# Millable_AS726x_Breakout.net
KiCad netlist of a schematic drawn in EAGLE
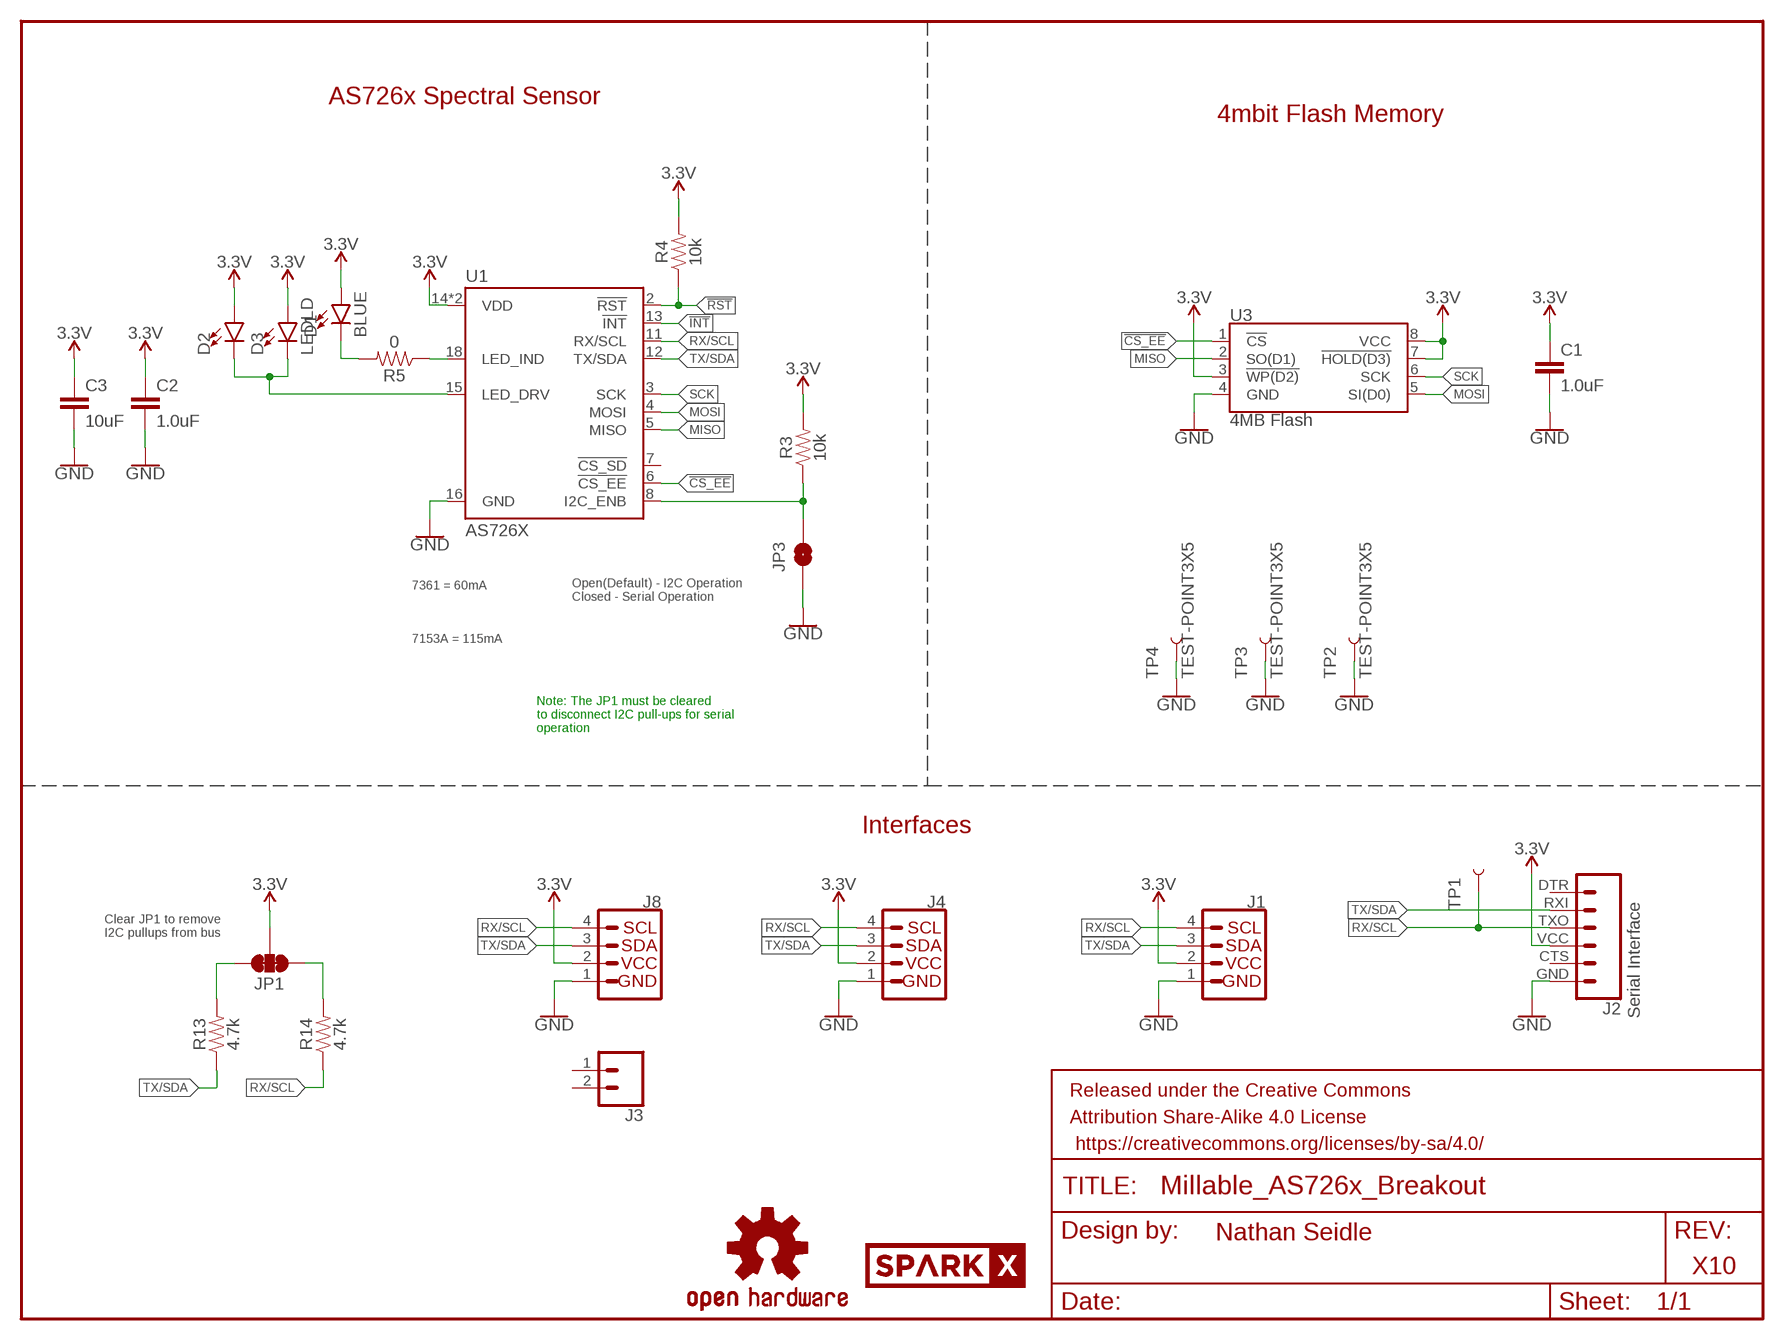
[diagram p0: schematic, sheet 1]

(export (version "E")
  (design (tool "Eeschema 10.0.6"))
  (components
    (comp (ref "C1")
      (value "1.0uF")
      (footprint "eagle-import:0603")
      (libsource (lib "eagle-import") (part "1.0UF-0603-16V-10%"))
    )
    (comp (ref "C2")
      (value "1.0uF")
      (footprint "eagle-import:0603")
      (libsource (lib "eagle-import") (part "1.0UF-0603-16V-10%"))
    )
    (comp (ref "C3")
      (value "10uF")
      (footprint "eagle-import:0603")
      (libsource (lib "eagle-import") (part "10UF-0603-6.3V-20%"))
    )
    (comp (ref "D1")
      (value "BLUE")
      (footprint "eagle-import:LED-0603")
      (libsource (lib "eagle-import") (part "LED-BLUE0603"))
    )
    (comp (ref "D2")
      (value "LED5MM")
      (footprint "eagle-import:LED_5MM")
      (libsource (lib "eagle-import") (part "LED5MM"))
    )
    (comp (ref "D3")
      (value "LEDLD")
      (footprint "eagle-import:SUPER_BRIGHT_SMD_LED_1206")
      (libsource (lib "eagle-import") (part "LEDLD"))
    )
    (comp (ref "FRAME1")
      (value "FRAME-LETTER")
      (footprint "eagle-import:CREATIVE_COMMONS")
      (libsource (lib "eagle-import") (part "FRAME-LETTER"))
    )
    (comp (ref "J1")
      (value "I2C_STANDARDJS-1MM")
      (footprint "eagle-import:1X04_1MM_RA")
      (libsource (lib "eagle-import") (part "I2C_STANDARDJS-1MM"))
    )
    (comp (ref "J2")
      (value "Serial Interface")
      (footprint "eagle-import:FTDI_BASIC")
      (libsource (lib "eagle-import") (part "6_PIN_SERIAL_CABLEPTH"))
    )
    (comp (ref "J3")
      (value "CONN_021X02_NO_SILK")
      (footprint "eagle-import:1X02_NO_SILK")
      (libsource (lib "eagle-import") (part "CONN_021X02_NO_SILK"))
    )
    (comp (ref "J4")
      (value "I2C_STANDARDJS-1MM")
      (footprint "eagle-import:1X04_1MM_RA")
      (libsource (lib "eagle-import") (part "I2C_STANDARDJS-1MM"))
    )
    (comp (ref "J8")
      (value "I2C_STANDARD_NO_SILK")
      (footprint "eagle-import:1X04_NO_SILK")
      (libsource (lib "eagle-import") (part "I2C_STANDARD_NO_SILK"))
    )
    (comp (ref "JP1")
      (value "JUMPER-SMT_3_2-NC_TRACE_SILK")
      (footprint "eagle-import:SMT-JUMPER_3_2-NC_TRACE_SILK")
      (libsource (lib "eagle-import") (part "JUMPER-SMT_3_2-NC_TRACE_SILK"))
    )
    (comp (ref "JP3")
      (value "JUMPER-SMT_2_NO-MILLABLE_NO-SILK")
      (footprint "eagle-import:SMT-JUMPER_2_NO_NO-SILK")
      (libsource (lib "eagle-import") (part "JUMPER-SMT_2_NO-MILLABLE_NO-SILK"))
    )
    (comp (ref "LOGO4")
      (value "OSHW-LOGOS")
      (footprint "eagle-import:OSHW-LOGO-S")
      (libsource (lib "eagle-import") (part "OSHW-LOGOS"))
    )
    (comp (ref "R3")
      (value "10k")
      (footprint "eagle-import:0603")
      (libsource (lib "eagle-import") (part "10KOHM-0603-1/10W-1%"))
    )
    (comp (ref "R4")
      (value "10k")
      (footprint "eagle-import:0603")
      (libsource (lib "eagle-import") (part "10KOHM-0603-1/10W-1%"))
    )
    (comp (ref "R5")
      (value "0")
      (footprint "eagle-import:0603")
      (libsource (lib "eagle-import") (part "0OHM-0603-1/10W-5%"))
    )
    (comp (ref "R13")
      (value "4.7k")
      (footprint "eagle-import:0603")
      (libsource (lib "eagle-import") (part "4.7KOHM-0603-1/10W-1%"))
    )
    (comp (ref "R14")
      (value "4.7k")
      (footprint "eagle-import:0603")
      (libsource (lib "eagle-import") (part "4.7KOHM-0603-1/10W-1%"))
    )
    (comp (ref "TP1")
      (value "TEST-POINT3X5")
      (footprint "eagle-import:PAD.03X.05")
      (libsource (lib "eagle-import") (part "TEST-POINT3X5"))
    )
    (comp (ref "TP2")
      (value "TEST-POINT3X5")
      (footprint "eagle-import:PAD.03X.05")
      (libsource (lib "eagle-import") (part "TEST-POINT3X5"))
    )
    (comp (ref "TP3")
      (value "TEST-POINT3X5")
      (footprint "eagle-import:PAD.03X.05")
      (libsource (lib "eagle-import") (part "TEST-POINT3X5"))
    )
    (comp (ref "TP4")
      (value "TEST-POINT3X5")
      (footprint "eagle-import:PAD.03X.05")
      (libsource (lib "eagle-import") (part "TEST-POINT3X5"))
    )
    (comp (ref "U$1")
      (value "SPARKX-LOGO3")
      (footprint "eagle-import:SPARKX-SMALL")
      (libsource (lib "eagle-import") (part "SPARKX-LOGO3"))
    )
    (comp (ref "U1")
      (value "AS726X")
      (footprint "eagle-import:LGA20")
      (libsource (lib "eagle-import") (part "AS726X"))
    )
    (comp (ref "U3")
      (value "4MB Flash")
      (footprint "eagle-import:SO08")
      (libsource (lib "eagle-import") (part "AT25SF041"))
    )
  )
  (nets
    (net (code "1") (name "/~{CS_EE}") (class "Default")
      (node (ref "U1") (pin "6") (pinfunction "~{CS_EE}_6") (pintype "bidirectional"))
      (node (ref "U3") (pin "1") (pinfunction "~{CS}_1") (pintype "bidirectional"))
    )
    (net (code "2") (name "/~{INT}") (class "Default")
      (node (ref "U1") (pin "13") (pinfunction "~{INT}_13") (pintype "bidirectional"))
    )
    (net (code "3") (name "/~{RST}") (class "Default")
      (node (ref "R4") (pin "1") (pinfunction "1_1") (pintype "passive"))
      (node (ref "U1") (pin "2") (pinfunction "~{RST}_2") (pintype "bidirectional"))
    )
    (net (code "4") (name "3.3V") (class "Default")
      (node (ref "C1") (pin "1") (pinfunction "1_1") (pintype "passive"))
      (node (ref "C2") (pin "1") (pinfunction "1_1") (pintype "passive"))
      (node (ref "C3") (pin "1") (pinfunction "1_1") (pintype "passive"))
      (node (ref "D1") (pin "A") (pinfunction "A_A") (pintype "passive"))
      (node (ref "D2") (pin "A") (pinfunction "A_A") (pintype "passive"))
      (node (ref "D3") (pin "A") (pinfunction "A_A") (pintype "passive"))
      (node (ref "J1") (pin "2") (pinfunction "VCC_2") (pintype "power_in"))
      (node (ref "J2") (pin "VCC") (pinfunction "4_VCC") (pintype "passive"))
      (node (ref "J4") (pin "2") (pinfunction "VCC_2") (pintype "power_in"))
      (node (ref "J8") (pin "2") (pinfunction "2_2") (pintype "power_in"))
      (node (ref "JP1") (pin "2") (pinfunction "2_2") (pintype "passive"))
      (node (ref "R3") (pin "2") (pinfunction "2_2") (pintype "passive"))
      (node (ref "R4") (pin "2") (pinfunction "2_2") (pintype "passive"))
      (node (ref "U1") (pin "14") (pinfunction "VDD_14") (pintype "bidirectional"))
      (node (ref "U1") (pin "17") (pinfunction "VDD_17") (pintype "bidirectional"))
      (node (ref "U3") (pin "3") (pinfunction "~{WP(D2})_3") (pintype "bidirectional"))
      (node (ref "U3") (pin "7") (pinfunction "~{HOLD(D3})_7") (pintype "bidirectional"))
      (node (ref "U3") (pin "8") (pinfunction "VCC_8") (pintype "bidirectional"))
    )
    (net (code "5") (name "GND") (class "Default")
      (node (ref "C1") (pin "2") (pinfunction "2_2") (pintype "passive"))
      (node (ref "C2") (pin "2") (pinfunction "2_2") (pintype "passive"))
      (node (ref "C3") (pin "2") (pinfunction "2_2") (pintype "passive"))
      (node (ref "J1") (pin "1") (pinfunction "GND_1") (pintype "power_in"))
      (node (ref "J2") (pin "GND") (pinfunction "6_GND") (pintype "passive"))
      (node (ref "J4") (pin "1") (pinfunction "GND_1") (pintype "power_in"))
      (node (ref "J8") (pin "1") (pinfunction "1_1") (pintype "power_in"))
      (node (ref "JP3") (pin "1") (pinfunction "1_1") (pintype "passive"))
      (node (ref "TP2") (pin "P$1") (pinfunction "1_P$1") (pintype "bidirectional"))
      (node (ref "TP3") (pin "P$1") (pinfunction "1_P$1") (pintype "bidirectional"))
      (node (ref "TP4") (pin "P$1") (pinfunction "1_P$1") (pintype "bidirectional"))
      (node (ref "U1") (pin "16") (pinfunction "GND_16") (pintype "bidirectional"))
      (node (ref "U3") (pin "4") (pinfunction "GND_4") (pintype "bidirectional"))
    )
    (net (code "6") (name "MISO") (class "Default")
      (node (ref "U1") (pin "5") (pinfunction "MISO_5") (pintype "bidirectional"))
      (node (ref "U3") (pin "2") (pinfunction "SO(D1)_2") (pintype "bidirectional"))
    )
    (net (code "7") (name "MOSI") (class "Default")
      (node (ref "U1") (pin "4") (pinfunction "MOSI_4") (pintype "bidirectional"))
      (node (ref "U3") (pin "5") (pinfunction "SI(D0)_5") (pintype "bidirectional"))
    )
    (net (code "8") (name "Net-(D1-PadC)") (class "Default")
      (node (ref "D1") (pin "C") (pinfunction "C_C") (pintype "passive"))
      (node (ref "R5") (pin "2") (pinfunction "2_2") (pintype "passive"))
    )
    (net (code "9") (name "Net-(D2-C)") (class "Default")
      (node (ref "D2") (pin "K") (pinfunction "C_K") (pintype "passive"))
      (node (ref "D3") (pin "C") (pinfunction "C_C") (pintype "passive"))
      (node (ref "U1") (pin "15") (pinfunction "LED_DRV_15") (pintype "bidirectional"))
    )
    (net (code "10") (name "Net-(JP1-Pad1)") (class "Default")
      (node (ref "JP1") (pin "1") (pinfunction "1_1") (pintype "passive"))
      (node (ref "R14") (pin "2") (pinfunction "2_2") (pintype "passive"))
    )
    (net (code "11") (name "Net-(JP1-Pad3)") (class "Default")
      (node (ref "JP1") (pin "3") (pinfunction "3_3") (pintype "passive"))
      (node (ref "R13") (pin "2") (pinfunction "2_2") (pintype "passive"))
    )
    (net (code "12") (name "Net-(U1-I2C_ENB)") (class "Default")
      (node (ref "JP3") (pin "2") (pinfunction "2_2") (pintype "passive"))
      (node (ref "R3") (pin "1") (pinfunction "1_1") (pintype "passive"))
      (node (ref "U1") (pin "8") (pinfunction "I2C_ENB_8") (pintype "bidirectional"))
    )
    (net (code "13") (name "Net-(U1-LED_IND)") (class "Default")
      (node (ref "R5") (pin "1") (pinfunction "1_1") (pintype "passive"))
      (node (ref "U1") (pin "18") (pinfunction "LED_IND_18") (pintype "bidirectional"))
    )
    (net (code "14") (name "RX{slash}SCL") (class "Default")
      (node (ref "J1") (pin "4") (pinfunction "SCL_4") (pintype "passive"))
      (node (ref "J2") (pin "TXO") (pinfunction "3_TXO") (pintype "passive"))
      (node (ref "J4") (pin "4") (pinfunction "SCL_4") (pintype "passive"))
      (node (ref "J8") (pin "4") (pinfunction "4_4") (pintype "passive"))
      (node (ref "R14") (pin "1") (pinfunction "1_1") (pintype "passive"))
      (node (ref "TP1") (pin "P$1") (pinfunction "1_P$1") (pintype "bidirectional"))
      (node (ref "U1") (pin "11") (pinfunction "RX/SCL_11") (pintype "bidirectional"))
    )
    (net (code "15") (name "SCK") (class "Default")
      (node (ref "U1") (pin "3") (pinfunction "SCK_3") (pintype "bidirectional"))
      (node (ref "U3") (pin "6") (pinfunction "SCK_6") (pintype "bidirectional"))
    )
    (net (code "16") (name "TX{slash}SDA") (class "Default")
      (node (ref "J1") (pin "3") (pinfunction "SDA_3") (pintype "passive"))
      (node (ref "J2") (pin "RXI") (pinfunction "2_RXI") (pintype "passive"))
      (node (ref "J4") (pin "3") (pinfunction "SDA_3") (pintype "passive"))
      (node (ref "J8") (pin "3") (pinfunction "3_3") (pintype "passive"))
      (node (ref "R13") (pin "1") (pinfunction "1_1") (pintype "passive"))
      (node (ref "U1") (pin "12") (pinfunction "TX/SDA_12") (pintype "bidirectional"))
    )
    (net (code "17") (name "unconnected-(J2-1-PadDTR)") (class "Default")
      (node (ref "J2") (pin "DTR") (pinfunction "1_DTR") (pintype "passive"))
    )
    (net (code "18") (name "unconnected-(J2-5-PadCTS)") (class "Default")
      (node (ref "J2") (pin "CTS") (pinfunction "5_CTS") (pintype "passive"))
    )
    (net (code "19") (name "unconnected-(J3-Pad1)") (class "Default")
      (node (ref "J3") (pin "1") (pinfunction "1_1") (pintype "passive"))
    )
    (net (code "20") (name "unconnected-(J3-Pad2)") (class "Default")
      (node (ref "J3") (pin "2") (pinfunction "2_2") (pintype "passive"))
    )
    (net (code "21") (name "unconnected-(U1-~{CS_SD}-Pad7)") (class "Default")
      (node (ref "U1") (pin "7") (pinfunction "~{CS_SD}_7") (pintype "bidirectional"))
    )
  )
)
